# 06_MCU.net
KiCad netlist of a schematic drawn in Altium Designer
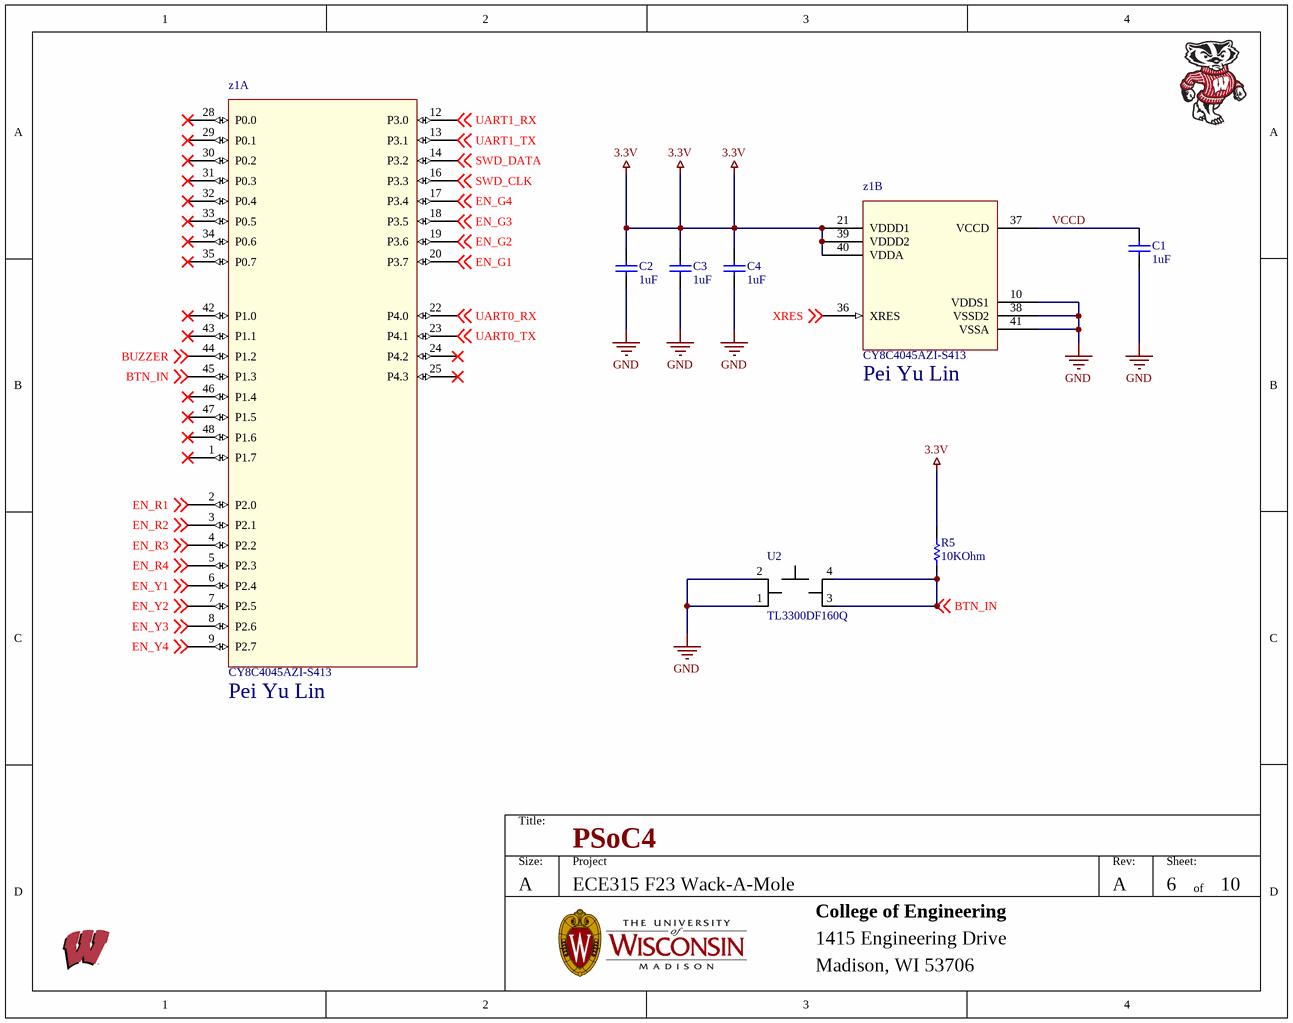
[diagram p0: 06_MCU.SchDoc]

(export (version "E")
  (design (tool "Eeschema 10.0.6"))
  (components
    (comp (ref "C1")
      (value "C1206C105K3RACTU")
      (footprint "CAPC3216X180X50ML20T25")
      (description "Chip Capacitor, 1 uF, +/- 10%, 25 V, -55 to 125 degC, 1206 (3216 Metric), RoHS, Tape and Reel")
      (fields
        (field (name "CAPACITANCE") "1uF")
        (field (name "MANUFACTURER") "Kemet")
        (field (name "TOLERANCE") "10%")
      )
      (libsource (lib "Altium Content Vault") (part "CAP-NP-2"))
    )
    (comp (ref "C2")
      (value "C1206C105K3RACTU")
      (footprint "CAPC3216X180X50ML20T25")
      (description "Chip Capacitor, 1 uF, +/- 10%, 25 V, -55 to 125 degC, 1206 (3216 Metric), RoHS, Tape and Reel")
      (fields
        (field (name "CAPACITANCE") "1uF")
        (field (name "MANUFACTURER") "Kemet")
        (field (name "TOLERANCE") "10%")
      )
      (libsource (lib "Altium Content Vault") (part "CAP-NP-2"))
    )
    (comp (ref "C3")
      (value "C1206C105K3RACTU")
      (footprint "CAPC3216X180X50ML20T25")
      (description "Chip Capacitor, 1 uF, +/- 10%, 25 V, -55 to 125 degC, 1206 (3216 Metric), RoHS, Tape and Reel")
      (fields
        (field (name "CAPACITANCE") "1uF")
        (field (name "MANUFACTURER") "Kemet")
        (field (name "TOLERANCE") "10%")
      )
      (libsource (lib "Altium Content Vault") (part "CAP-NP-2"))
    )
    (comp (ref "C4")
      (value "C1206C105K3RACTU")
      (footprint "CAPC3216X180X50ML20T25")
      (description "Chip Capacitor, 1 uF, +/- 10%, 25 V, -55 to 125 degC, 1206 (3216 Metric), RoHS, Tape and Reel")
      (fields
        (field (name "CAPACITANCE") "1uF")
        (field (name "MANUFACTURER") "Kemet")
        (field (name "TOLERANCE") "10%")
      )
      (libsource (lib "Altium Content Vault") (part "CAP-NP-2"))
    )
    (comp (ref "R5")
      (value "RC1206FR-0710KL")
      (footprint "RESC3116X65X40ML10T20")
      (description "Chip Resistor, 10 KOhm, +/- 1%, 0.25 W, -55 to 155 degC, 1206 (3216 Metric), RoHS, Tape and Reel")
      (fields
        (field (name "TOLERANCE") "1%")
        (field (name "RESISTANCE") "10KOhm")
        (field (name "MANUFACTURER") "Yageo")
      )
      (libsource (lib "Altium Content Vault") (part "RES-2"))
    )
    (comp (ref "U2")
      (value "TL3300DF160Q")
      (footprint "TL3300DF160Q")
      (description "Switch Tactile OFF (ON) SPST Round Button Gull Wing 0.05A 12VDC 1.57N SMD")
      (fields (field (name "MANUFACTURER") "E-Switch"))
      (libsource (lib "ECE315") (part "TL3300DF160Q"))
    )
    (comp (ref "z1")
      (value "CY8C4045AZI-S413")
      (footprint "TQFP48_7X7")
      (description "ARM Microcontrollers - MCU PSoC4")
      (fields (field (name "DRAWN BY") "Pei Yu Lin"))
      (libsource (lib "ECE315") (part "CY8C4045AZI-S413"))
    )
  )
  (nets
    (net (code "1") (name "/VCCD") (class "Default")
      (node (ref "C1") (pin "1") (pinfunction "1_1") (pintype "passive"))
      (node (ref "z1") (pin "37") (pinfunction "VCCD_37") (pintype "power_in"))
    )
    (net (code "2") (name "3.3V") (class "Default")
      (node (ref "C2") (pin "1") (pinfunction "1_1") (pintype "passive"))
      (node (ref "C3") (pin "1") (pinfunction "1_1") (pintype "passive"))
      (node (ref "C4") (pin "1") (pinfunction "1_1") (pintype "passive"))
      (node (ref "R5") (pin "2") (pinfunction "2_2") (pintype "passive"))
      (node (ref "z1") (pin "21") (pinfunction "VDDD1_21") (pintype "power_in"))
      (node (ref "z1") (pin "39") (pinfunction "VDDD2_39") (pintype "power_in"))
      (node (ref "z1") (pin "40") (pinfunction "VDDA_40") (pintype "power_in"))
    )
    (net (code "3") (name "BTN_IN") (class "Default")
      (node (ref "R5") (pin "1") (pinfunction "1_1") (pintype "passive"))
      (node (ref "U2") (pin "3") (pinfunction "3_3") (pintype "passive"))
      (node (ref "U2") (pin "4") (pinfunction "VCCIO_4") (pintype "passive"))
      (node (ref "z1") (pin "45") (pinfunction "P1.3_45") (pintype "bidirectional"))
    )
    (net (code "4") (name "BUZZER") (class "Default")
      (node (ref "z1") (pin "44") (pinfunction "P1.2_44") (pintype "bidirectional"))
    )
    (net (code "5") (name "EN_G1") (class "Default")
      (node (ref "z1") (pin "20") (pinfunction "P3.7_20") (pintype "bidirectional"))
    )
    (net (code "6") (name "EN_G2") (class "Default")
      (node (ref "z1") (pin "19") (pinfunction "P3.6_19") (pintype "bidirectional"))
    )
    (net (code "7") (name "EN_G3") (class "Default")
      (node (ref "z1") (pin "18") (pinfunction "P3.5_18") (pintype "bidirectional"))
    )
    (net (code "8") (name "EN_G4") (class "Default")
      (node (ref "z1") (pin "17") (pinfunction "P3.4_17") (pintype "bidirectional"))
    )
    (net (code "9") (name "EN_R1") (class "Default")
      (node (ref "z1") (pin "2") (pinfunction "P2.0_2") (pintype "bidirectional"))
    )
    (net (code "10") (name "EN_R2") (class "Default")
      (node (ref "z1") (pin "3") (pinfunction "P2.1_3") (pintype "bidirectional"))
    )
    (net (code "11") (name "EN_R3") (class "Default")
      (node (ref "z1") (pin "4") (pinfunction "P2.2_4") (pintype "bidirectional"))
    )
    (net (code "12") (name "EN_R4") (class "Default")
      (node (ref "z1") (pin "5") (pinfunction "P2.3_5") (pintype "bidirectional"))
    )
    (net (code "13") (name "EN_Y1") (class "Default")
      (node (ref "z1") (pin "6") (pinfunction "P2.4_6") (pintype "bidirectional"))
    )
    (net (code "14") (name "EN_Y2") (class "Default")
      (node (ref "z1") (pin "7") (pinfunction "P2.5_7") (pintype "bidirectional"))
    )
    (net (code "15") (name "EN_Y3") (class "Default")
      (node (ref "z1") (pin "8") (pinfunction "P2.6_8") (pintype "bidirectional"))
    )
    (net (code "16") (name "EN_Y4") (class "Default")
      (node (ref "z1") (pin "9") (pinfunction "P2.7_9") (pintype "bidirectional"))
    )
    (net (code "17") (name "GND") (class "Default")
      (node (ref "C1") (pin "2") (pinfunction "2_2") (pintype "passive"))
      (node (ref "C2") (pin "2") (pinfunction "2_2") (pintype "passive"))
      (node (ref "C3") (pin "2") (pinfunction "2_2") (pintype "passive"))
      (node (ref "C4") (pin "2") (pinfunction "2_2") (pintype "passive"))
      (node (ref "U2") (pin "1") (pinfunction "1_1") (pintype "passive"))
      (node (ref "U2") (pin "2") (pinfunction "2_2") (pintype "passive"))
      (node (ref "z1") (pin "10") (pinfunction "VDDS1_10") (pintype "power_in"))
      (node (ref "z1") (pin "38") (pinfunction "VSSD2_38") (pintype "power_in"))
      (node (ref "z1") (pin "41") (pinfunction "VSSA_41") (pintype "power_in"))
    )
    (net (code "18") (name "SWD_CLK") (class "Default")
      (node (ref "z1") (pin "16") (pinfunction "P3.3_16") (pintype "bidirectional"))
    )
    (net (code "19") (name "SWD_DATA") (class "Default")
      (node (ref "z1") (pin "14") (pinfunction "P3.2_14") (pintype "bidirectional"))
    )
    (net (code "20") (name "UART0_RX") (class "Default")
      (node (ref "z1") (pin "22") (pinfunction "P4.0_22") (pintype "bidirectional"))
    )
    (net (code "21") (name "UART0_TX") (class "Default")
      (node (ref "z1") (pin "23") (pinfunction "P4.1_23") (pintype "bidirectional"))
    )
    (net (code "22") (name "UART1_RX") (class "Default")
      (node (ref "z1") (pin "12") (pinfunction "P3.0_12") (pintype "bidirectional"))
    )
    (net (code "23") (name "UART1_TX") (class "Default")
      (node (ref "z1") (pin "13") (pinfunction "P3.1_13") (pintype "bidirectional"))
    )
    (net (code "24") (name "XRES") (class "Default")
      (node (ref "z1") (pin "36") (pinfunction "XRES_36") (pintype "input"))
    )
    (net (code "25") (name "unconnected-(z1A-P0.0-Pad28)") (class "Default")
      (node (ref "z1") (pin "28") (pinfunction "P0.0_28") (pintype "bidirectional+no_connect"))
    )
    (net (code "26") (name "unconnected-(z1A-P0.1-Pad29)") (class "Default")
      (node (ref "z1") (pin "29") (pinfunction "P0.1_29") (pintype "bidirectional+no_connect"))
    )
    (net (code "27") (name "unconnected-(z1A-P0.2-Pad30)") (class "Default")
      (node (ref "z1") (pin "30") (pinfunction "P0.2_30") (pintype "bidirectional+no_connect"))
    )
    (net (code "28") (name "unconnected-(z1A-P0.3-Pad31)") (class "Default")
      (node (ref "z1") (pin "31") (pinfunction "P0.3_31") (pintype "bidirectional+no_connect"))
    )
    (net (code "29") (name "unconnected-(z1A-P0.4-Pad32)") (class "Default")
      (node (ref "z1") (pin "32") (pinfunction "P0.4_32") (pintype "bidirectional+no_connect"))
    )
    (net (code "30") (name "unconnected-(z1A-P0.5-Pad33)") (class "Default")
      (node (ref "z1") (pin "33") (pinfunction "P0.5_33") (pintype "bidirectional+no_connect"))
    )
    (net (code "31") (name "unconnected-(z1A-P0.6-Pad34)") (class "Default")
      (node (ref "z1") (pin "34") (pinfunction "P0.6_34") (pintype "bidirectional+no_connect"))
    )
    (net (code "32") (name "unconnected-(z1A-P0.7-Pad35)") (class "Default")
      (node (ref "z1") (pin "35") (pinfunction "P0.7_35") (pintype "bidirectional+no_connect"))
    )
    (net (code "33") (name "unconnected-(z1A-P1.0-Pad42)") (class "Default")
      (node (ref "z1") (pin "42") (pinfunction "P1.0_42") (pintype "bidirectional+no_connect"))
    )
    (net (code "34") (name "unconnected-(z1A-P1.1-Pad43)") (class "Default")
      (node (ref "z1") (pin "43") (pinfunction "P1.1_43") (pintype "bidirectional+no_connect"))
    )
    (net (code "35") (name "unconnected-(z1A-P1.4-Pad46)") (class "Default")
      (node (ref "z1") (pin "46") (pinfunction "P1.4_46") (pintype "bidirectional+no_connect"))
    )
    (net (code "36") (name "unconnected-(z1A-P1.5-Pad47)") (class "Default")
      (node (ref "z1") (pin "47") (pinfunction "P1.5_47") (pintype "bidirectional+no_connect"))
    )
    (net (code "37") (name "unconnected-(z1A-P1.6-Pad48)") (class "Default")
      (node (ref "z1") (pin "48") (pinfunction "P1.6_48") (pintype "bidirectional+no_connect"))
    )
    (net (code "38") (name "unconnected-(z1A-P1.7-Pad1)") (class "Default")
      (node (ref "z1") (pin "1") (pinfunction "P1.7_1") (pintype "bidirectional+no_connect"))
    )
    (net (code "39") (name "unconnected-(z1A-P4.2-Pad24)") (class "Default")
      (node (ref "z1") (pin "24") (pinfunction "P4.2_24") (pintype "bidirectional+no_connect"))
    )
    (net (code "40") (name "unconnected-(z1A-P4.3-Pad25)") (class "Default")
      (node (ref "z1") (pin "25") (pinfunction "P4.3_25") (pintype "bidirectional+no_connect"))
    )
  )
)
